# CC40CartReader.net
KiCad netlist of a schematic drawn in EAGLE
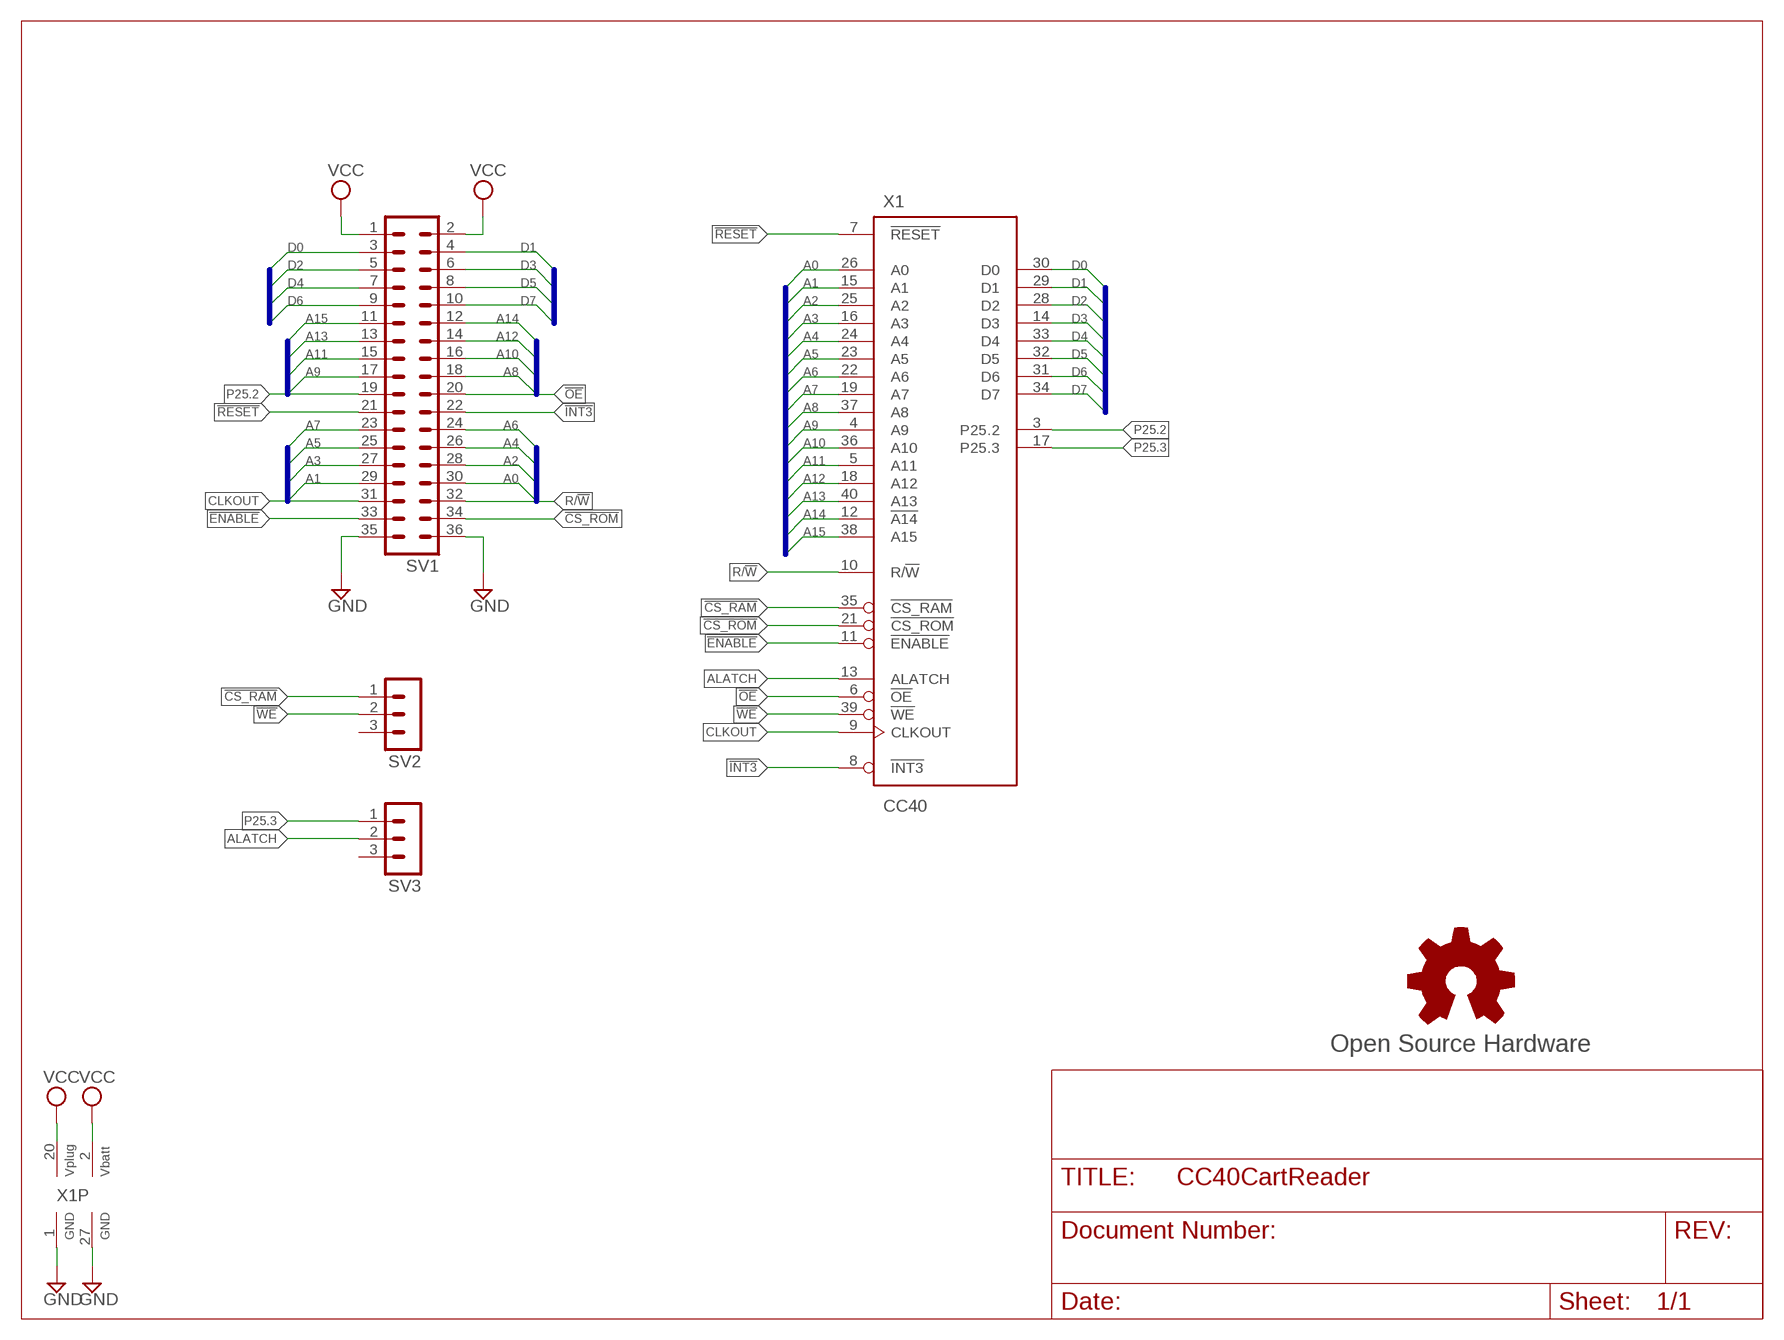
[diagram p0: schematic, sheet 1]

(export (version "E")
  (design (tool "Eeschema 10.0.6"))
  (components
    (comp (ref "GOLD_ORB_SM1")
      (value "Open Source Hardware")
      (footprint "eagle-import:OSHW_8MM")
      (libsource (lib "eagle-import") (part "OSHWLOGOLOGO8MM"))
    )
    (comp (ref "SV1")
      (value "MA18-2")
      (footprint "eagle-import:MA18-2")
      (libsource (lib "eagle-import") (part "MA18-2"))
    )
    (comp (ref "SV2")
      (value "MA03-1")
      (footprint "eagle-import:MA03-1")
      (libsource (lib "eagle-import") (part "MA03-1"))
    )
    (comp (ref "SV3")
      (value "MA03-1")
      (footprint "eagle-import:MA03-1")
      (libsource (lib "eagle-import") (part "MA03-1"))
    )
    (comp (ref "X1")
      (value "CC40")
      (footprint "eagle-import:FE20-2(.050)SHORT")
      (libsource (lib "eagle-import") (part "EXPANSION_PORT_CC40C"))
    )
  )
  (nets
    (net (code "1") (name "/A0") (class "Default")
      (node (ref "SV1") (pin "30") (pinfunction "30_30") (pintype "passive"))
      (node (ref "X1") (pin "26") (pinfunction "A0_26") (pintype "output"))
    )
    (net (code "2") (name "/A1") (class "Default")
      (node (ref "SV1") (pin "29") (pinfunction "29_29") (pintype "passive"))
      (node (ref "X1") (pin "15") (pinfunction "A1_15") (pintype "output"))
    )
    (net (code "3") (name "/A2") (class "Default")
      (node (ref "SV1") (pin "28") (pinfunction "28_28") (pintype "passive"))
      (node (ref "X1") (pin "25") (pinfunction "A2_25") (pintype "output"))
    )
    (net (code "4") (name "/A3") (class "Default")
      (node (ref "SV1") (pin "27") (pinfunction "27_27") (pintype "passive"))
      (node (ref "X1") (pin "16") (pinfunction "A3_16") (pintype "output"))
    )
    (net (code "5") (name "/A4") (class "Default")
      (node (ref "SV1") (pin "26") (pinfunction "26_26") (pintype "passive"))
      (node (ref "X1") (pin "24") (pinfunction "A4_24") (pintype "output"))
    )
    (net (code "6") (name "/A5") (class "Default")
      (node (ref "SV1") (pin "25") (pinfunction "25_25") (pintype "passive"))
      (node (ref "X1") (pin "23") (pinfunction "A5_23") (pintype "output"))
    )
    (net (code "7") (name "/A6") (class "Default")
      (node (ref "SV1") (pin "24") (pinfunction "24_24") (pintype "passive"))
      (node (ref "X1") (pin "22") (pinfunction "A6_22") (pintype "output"))
    )
    (net (code "8") (name "/A7") (class "Default")
      (node (ref "SV1") (pin "23") (pinfunction "23_23") (pintype "passive"))
      (node (ref "X1") (pin "19") (pinfunction "A7_19") (pintype "output"))
    )
    (net (code "9") (name "/A8") (class "Default")
      (node (ref "SV1") (pin "18") (pinfunction "18_18") (pintype "passive"))
      (node (ref "X1") (pin "37") (pinfunction "A8_37") (pintype "output"))
    )
    (net (code "10") (name "/A9") (class "Default")
      (node (ref "SV1") (pin "17") (pinfunction "17_17") (pintype "passive"))
      (node (ref "X1") (pin "4") (pinfunction "A9_4") (pintype "output"))
    )
    (net (code "11") (name "/A10") (class "Default")
      (node (ref "SV1") (pin "16") (pinfunction "16_16") (pintype "passive"))
      (node (ref "X1") (pin "36") (pinfunction "A10_36") (pintype "passive"))
    )
    (net (code "12") (name "/A11") (class "Default")
      (node (ref "SV1") (pin "15") (pinfunction "15_15") (pintype "passive"))
      (node (ref "X1") (pin "5") (pinfunction "A11_5") (pintype "output"))
    )
    (net (code "13") (name "/A12") (class "Default")
      (node (ref "SV1") (pin "14") (pinfunction "14_14") (pintype "passive"))
      (node (ref "X1") (pin "18") (pinfunction "A12_18") (pintype "output"))
    )
    (net (code "14") (name "/A13") (class "Default")
      (node (ref "SV1") (pin "13") (pinfunction "13_13") (pintype "passive"))
      (node (ref "X1") (pin "40") (pinfunction "A13_40") (pintype "output"))
    )
    (net (code "15") (name "/A14") (class "Default")
      (node (ref "SV1") (pin "12") (pinfunction "12_12") (pintype "passive"))
      (node (ref "X1") (pin "12") (pinfunction "~{A14}_12") (pintype "output"))
    )
    (net (code "16") (name "/A15") (class "Default")
      (node (ref "SV1") (pin "11") (pinfunction "11_11") (pintype "passive"))
      (node (ref "X1") (pin "38") (pinfunction "A15_38") (pintype "output"))
    )
    (net (code "17") (name "/D0") (class "Default")
      (node (ref "SV1") (pin "3") (pinfunction "3_3") (pintype "passive"))
      (node (ref "X1") (pin "30") (pinfunction "D0_30") (pintype "bidirectional"))
    )
    (net (code "18") (name "/D1") (class "Default")
      (node (ref "SV1") (pin "4") (pinfunction "4_4") (pintype "passive"))
      (node (ref "X1") (pin "29") (pinfunction "D1_29") (pintype "bidirectional"))
    )
    (net (code "19") (name "/D2") (class "Default")
      (node (ref "SV1") (pin "5") (pinfunction "5_5") (pintype "passive"))
      (node (ref "X1") (pin "28") (pinfunction "D2_28") (pintype "bidirectional"))
    )
    (net (code "20") (name "/D3") (class "Default")
      (node (ref "SV1") (pin "6") (pinfunction "6_6") (pintype "passive"))
      (node (ref "X1") (pin "14") (pinfunction "D3_14") (pintype "bidirectional"))
    )
    (net (code "21") (name "/D4") (class "Default")
      (node (ref "SV1") (pin "7") (pinfunction "7_7") (pintype "passive"))
      (node (ref "X1") (pin "33") (pinfunction "D4_33") (pintype "bidirectional"))
    )
    (net (code "22") (name "/D5") (class "Default")
      (node (ref "SV1") (pin "8") (pinfunction "8_8") (pintype "passive"))
      (node (ref "X1") (pin "32") (pinfunction "D5_32") (pintype "bidirectional"))
    )
    (net (code "23") (name "/D6") (class "Default")
      (node (ref "SV1") (pin "9") (pinfunction "9_9") (pintype "passive"))
      (node (ref "X1") (pin "31") (pinfunction "D6_31") (pintype "bidirectional"))
    )
    (net (code "24") (name "/D7") (class "Default")
      (node (ref "SV1") (pin "10") (pinfunction "10_10") (pintype "passive"))
      (node (ref "X1") (pin "34") (pinfunction "D7_34") (pintype "bidirectional"))
    )
    (net (code "25") (name "/R{slash}~{W}") (class "Default")
      (node (ref "SV1") (pin "32") (pinfunction "32_32") (pintype "passive"))
      (node (ref "X1") (pin "10") (pinfunction "R/~{W}_10") (pintype "output"))
    )
    (net (code "26") (name "/~{CS_RAM}") (class "Default")
      (node (ref "SV2") (pin "1") (pinfunction "1_1") (pintype "passive"))
      (node (ref "X1") (pin "35") (pinfunction "~{CS_RAM}_35") (pintype "output"))
    )
    (net (code "27") (name "/~{CS_ROM}") (class "Default")
      (node (ref "SV1") (pin "34") (pinfunction "34_34") (pintype "passive"))
      (node (ref "X1") (pin "21") (pinfunction "~{CS_ROM}_21") (pintype "output"))
    )
    (net (code "28") (name "/~{ENABLE}") (class "Default")
      (node (ref "SV1") (pin "33") (pinfunction "33_33") (pintype "passive"))
      (node (ref "X1") (pin "11") (pinfunction "~{ENABLE}_11") (pintype "output"))
    )
    (net (code "29") (name "/~{INT3}") (class "Default")
      (node (ref "SV1") (pin "22") (pinfunction "22_22") (pintype "passive"))
      (node (ref "X1") (pin "8") (pinfunction "~{INT3}_8") (pintype "open_collector"))
    )
    (net (code "30") (name "/~{OE}") (class "Default")
      (node (ref "SV1") (pin "20") (pinfunction "20_20") (pintype "passive"))
      (node (ref "X1") (pin "6") (pinfunction "~{OE}_6") (pintype "output"))
    )
    (net (code "31") (name "/~{RESET}") (class "Default")
      (node (ref "SV1") (pin "21") (pinfunction "21_21") (pintype "passive"))
      (node (ref "X1") (pin "7") (pinfunction "~{RESET}_7") (pintype "open_collector"))
    )
    (net (code "32") (name "/~{WE}") (class "Default")
      (node (ref "SV2") (pin "2") (pinfunction "2_2") (pintype "passive"))
      (node (ref "X1") (pin "39") (pinfunction "~{WE}_39") (pintype "output"))
    )
    (net (code "33") (name "ALATCH") (class "Default")
      (node (ref "SV3") (pin "2") (pinfunction "2_2") (pintype "passive"))
      (node (ref "X1") (pin "13") (pinfunction "ALATCH_13") (pintype "output"))
    )
    (net (code "34") (name "CLKOUT") (class "Default")
      (node (ref "SV1") (pin "31") (pinfunction "31_31") (pintype "passive"))
      (node (ref "X1") (pin "9") (pinfunction "CLKOUT_9") (pintype "output"))
    )
    (net (code "35") (name "GND") (class "Default")
      (node (ref "SV1") (pin "35") (pinfunction "35_35") (pintype "passive"))
      (node (ref "SV1") (pin "36") (pinfunction "36_36") (pintype "passive"))
      (node (ref "X1") (pin "1") (pinfunction "GND_1") (pintype "power_in"))
      (node (ref "X1") (pin "27") (pinfunction "GND_27") (pintype "power_in"))
    )
    (net (code "36") (name "P25.2") (class "Default")
      (node (ref "SV1") (pin "19") (pinfunction "19_19") (pintype "passive"))
      (node (ref "X1") (pin "3") (pinfunction "P25.2_3") (pintype "bidirectional"))
    )
    (net (code "37") (name "P25.3") (class "Default")
      (node (ref "SV3") (pin "1") (pinfunction "1_1") (pintype "passive"))
      (node (ref "X1") (pin "17") (pinfunction "P25.3_17") (pintype "bidirectional"))
    )
    (net (code "38") (name "VCC") (class "Default")
      (node (ref "SV1") (pin "1") (pinfunction "1_1") (pintype "passive"))
      (node (ref "SV1") (pin "2") (pinfunction "2_2") (pintype "passive"))
      (node (ref "X1") (pin "2") (pinfunction "VBATT_2") (pintype "power_in"))
      (node (ref "X1") (pin "20") (pinfunction "VPLUG_20") (pintype "power_in"))
    )
    (net (code "39") (name "unconnected-(SV2-Pad3)") (class "Default")
      (node (ref "SV2") (pin "3") (pinfunction "3_3") (pintype "passive"))
    )
    (net (code "40") (name "unconnected-(SV3-Pad3)") (class "Default")
      (node (ref "SV3") (pin "3") (pinfunction "3_3") (pintype "passive"))
    )
  )
)
